# PH10EA2332-1.net
KiCad netlist of a schematic drawn in Altium Designer
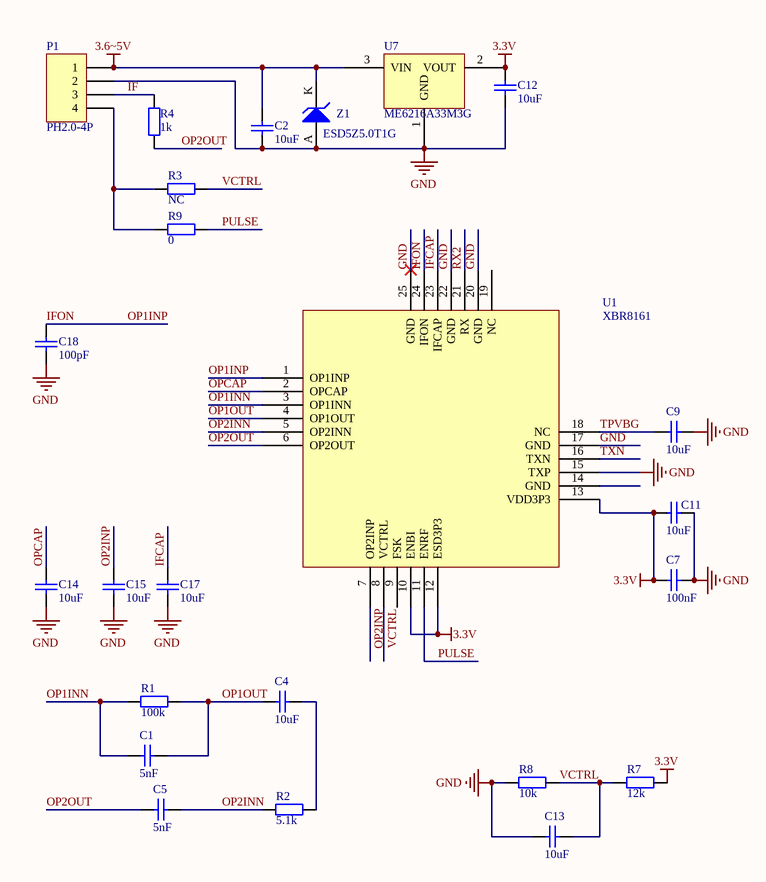
[diagram p0: PH10EA2332-1.SchDoc]

(export (version "E")
  (design (tool "Eeschema 10.0.6"))
  (components
    (comp (ref "C1")
      (value "5nF")
      (footprint "C0402")
      (description "Capacitor")
      (fields (field (name "PUBLISHER") "Altium Limited"))
      (libsource (lib "Miscellaneous Devices") (part "Cap"))
    )
    (comp (ref "C2")
      (value "10uF")
      (footprint "C0402")
      (description "Capacitor")
      (fields (field (name "PUBLISHER") "Altium Limited"))
      (libsource (lib "Miscellaneous Devices") (part "Cap"))
    )
    (comp (ref "C4")
      (value "10uF")
      (footprint "C0402")
      (description "Capacitor")
      (fields (field (name "PUBLISHER") "Altium Limited"))
      (libsource (lib "Miscellaneous Devices") (part "Cap"))
    )
    (comp (ref "C5")
      (value "5nF")
      (footprint "C0402")
      (description "Capacitor")
      (fields (field (name "PUBLISHER") "Altium Limited"))
      (libsource (lib "Miscellaneous Devices") (part "Cap"))
    )
    (comp (ref "C7")
      (value "100nF")
      (footprint "C0402")
      (description "Capacitor")
      (fields (field (name "PUBLISHER") "Altium Limited"))
      (libsource (lib "Miscellaneous Devices") (part "Cap"))
    )
    (comp (ref "C9")
      (value "10uF")
      (footprint "C0402")
      (description "Capacitor")
      (fields (field (name "PUBLISHER") "Altium Limited"))
      (libsource (lib "Miscellaneous Devices") (part "Cap"))
    )
    (comp (ref "C11")
      (value "10uF")
      (footprint "C0402")
      (description "Capacitor")
      (fields (field (name "PUBLISHER") "Altium Limited"))
      (libsource (lib "Miscellaneous Devices") (part "Cap"))
    )
    (comp (ref "C12")
      (value "10uF")
      (footprint "C0402")
      (description "Capacitor")
      (fields (field (name "PUBLISHER") "Altium Limited"))
      (libsource (lib "Miscellaneous Devices") (part "Cap"))
    )
    (comp (ref "C13")
      (value "10uF")
      (footprint "C0402")
      (description "Capacitor")
      (fields (field (name "PUBLISHER") "Altium Limited"))
      (libsource (lib "Miscellaneous Devices") (part "Cap"))
    )
    (comp (ref "C14")
      (value "10uF")
      (footprint "C0402")
      (description "Capacitor")
      (fields (field (name "PUBLISHER") "Altium Limited"))
      (libsource (lib "Miscellaneous Devices") (part "Cap"))
    )
    (comp (ref "C15")
      (value "10uF")
      (footprint "C0402")
      (description "Capacitor")
      (fields (field (name "PUBLISHER") "Altium Limited"))
      (libsource (lib "Miscellaneous Devices") (part "Cap"))
    )
    (comp (ref "C17")
      (value "10uF")
      (footprint "C0402")
      (description "Capacitor")
      (fields (field (name "PUBLISHER") "Altium Limited"))
      (libsource (lib "Miscellaneous Devices") (part "Cap"))
    )
    (comp (ref "C18")
      (value "100pF")
      (footprint "C0402")
      (description "Capacitor")
      (fields (field (name "PUBLISHER") "Altium Limited"))
      (libsource (lib "Miscellaneous Devices") (part "Cap"))
    )
    (comp (ref "P1")
      (value "PH2.0-4P")
      (footprint "PH2.0-4P")
      (description "Header, 4-Pin")
      (fields (field (name "PUBLISHER") "Altium Limited"))
      (libsource (lib "*") (part "Header 4"))
    )
    (comp (ref "R1")
      (value "100k")
      (footprint "R0402")
      (description "Resistor")
      (fields (field (name "PUBLISHER") "Altium Limited"))
      (libsource (lib "Miscellaneous Devices") (part "Res2"))
    )
    (comp (ref "R2")
      (value "5.1k")
      (footprint "R0402")
      (description "Resistor")
      (fields (field (name "PUBLISHER") "Altium Limited"))
      (libsource (lib "") (part "Res2_2"))
    )
    (comp (ref "R3")
      (value "NC")
      (footprint "R0402")
      (description "Resistor")
      (fields (field (name "PUBLISHER") "Altium Limited"))
      (libsource (lib "") (part "Res2_2"))
    )
    (comp (ref "R4")
      (value "1k")
      (footprint "R0402")
      (description "Resistor")
      (fields (field (name "PUBLISHER") "Altium Limited"))
      (libsource (lib "") (part "Res2_1"))
    )
    (comp (ref "R7")
      (value "12k")
      (footprint "R0402")
      (description "Resistor")
      (fields (field (name "PUBLISHER") "Altium Limited"))
      (libsource (lib "") (part "Res2_2"))
    )
    (comp (ref "R8")
      (value "10k")
      (footprint "R0402")
      (description "Resistor")
      (fields (field (name "PUBLISHER") "Altium Limited"))
      (libsource (lib "") (part "Res2_2"))
    )
    (comp (ref "R9")
      (value "0")
      (footprint "R0402")
      (description "Resistor")
      (fields (field (name "PUBLISHER") "Altium Limited"))
      (libsource (lib "Miscellaneous Devices") (part "Res2"))
    )
    (comp (ref "U1")
      (value "XBR8161")
      (footprint "QFN24")
      (libsource (lib "altium-import") (part "root_0_XBR8161_"))
    )
    (comp (ref "U7")
      (value "ME6216A33M3G")
      (footprint "SOT-23-L")
      (libsource (lib "Schlib1") (part "SSP6206"))
    )
    (comp (ref "Z1")
      (value "ESD5Z5.0T1G")
      (footprint "SOD-523")
      (description "Zener Diode")
      (fields (field (name "PUBLISHER") "Altium Limited"))
      (libsource (lib "Miscellaneous Devices") (part "D Zener"))
    )
  )
  (nets
    (net (code "1") (name "/IF") (class "Default")
      (node (ref "P1") (pin "3") (pinfunction "3_3") (pintype "passive"))
      (node (ref "R4") (pin "1") (pinfunction "1_1") (pintype "passive"))
    )
    (net (code "2") (name "/IFCAP") (class "Default")
      (node (ref "C17") (pin "2") (pinfunction "2_2") (pintype "passive"))
      (node (ref "U1") (pin "23") (pinfunction "IFCAP_23") (pintype "passive"))
    )
    (net (code "3") (name "/IFON") (class "Default")
      (node (ref "C18") (pin "2") (pinfunction "2_2") (pintype "passive"))
      (node (ref "U1") (pin "1") (pinfunction "OP1INP_1") (pintype "passive"))
      (node (ref "U1") (pin "24") (pinfunction "IFON_24") (pintype "passive"))
    )
    (net (code "4") (name "/OP1INN") (class "Default")
      (node (ref "C1") (pin "2") (pinfunction "2_2") (pintype "passive"))
      (node (ref "R1") (pin "1") (pinfunction "1_1") (pintype "passive"))
      (node (ref "U1") (pin "3") (pinfunction "OP1INN_3") (pintype "passive"))
    )
    (net (code "5") (name "/OP1OUT") (class "Default")
      (node (ref "C1") (pin "1") (pinfunction "1_1") (pintype "passive"))
      (node (ref "C4") (pin "2") (pinfunction "2_2") (pintype "passive"))
      (node (ref "R1") (pin "2") (pinfunction "2_2") (pintype "passive"))
      (node (ref "U1") (pin "4") (pinfunction "OP1OUT_4") (pintype "passive"))
    )
    (net (code "6") (name "/OP2INN") (class "Default")
      (node (ref "C5") (pin "2") (pinfunction "2_2") (pintype "passive"))
      (node (ref "R2") (pin "2") (pinfunction "2_2") (pintype "passive"))
      (node (ref "U1") (pin "5") (pinfunction "OP2INN_5") (pintype "passive"))
    )
    (net (code "7") (name "/OP2INP") (class "Default")
      (node (ref "C15") (pin "1") (pinfunction "1_1") (pintype "passive"))
      (node (ref "U1") (pin "7") (pinfunction "OP2INP_7") (pintype "passive"))
    )
    (net (code "8") (name "/OP2OUT") (class "Default")
      (node (ref "C5") (pin "1") (pinfunction "1_1") (pintype "passive"))
      (node (ref "R4") (pin "2") (pinfunction "2_2") (pintype "passive"))
      (node (ref "U1") (pin "6") (pinfunction "OP2OUT_6") (pintype "passive"))
    )
    (net (code "9") (name "/OPCAP") (class "Default")
      (node (ref "C14") (pin "2") (pinfunction "2_2") (pintype "passive"))
      (node (ref "U1") (pin "2") (pinfunction "OPCAP_2") (pintype "passive"))
    )
    (net (code "10") (name "/PULSE") (class "Default")
      (node (ref "R9") (pin "2") (pinfunction "2_2") (pintype "passive"))
      (node (ref "U1") (pin "11") (pinfunction "ENRF_11") (pintype "passive"))
    )
    (net (code "11") (name "/RX2") (class "Default")
      (node (ref "U1") (pin "21") (pinfunction "RX_21") (pintype "passive"))
    )
    (net (code "12") (name "/TPVBG") (class "Default")
      (node (ref "C9") (pin "2") (pinfunction "2_2") (pintype "passive"))
      (node (ref "U1") (pin "18") (pinfunction "NC_18") (pintype "passive"))
    )
    (net (code "13") (name "/TXN") (class "Default")
      (node (ref "U1") (pin "16") (pinfunction "TXN_16") (pintype "passive"))
    )
    (net (code "14") (name "/VCTRL") (class "Default")
      (node (ref "C13") (pin "1") (pinfunction "1_1") (pintype "passive"))
      (node (ref "R3") (pin "1") (pinfunction "1_1") (pintype "passive"))
      (node (ref "R7") (pin "2") (pinfunction "2_2") (pintype "passive"))
      (node (ref "R8") (pin "1") (pinfunction "1_1") (pintype "passive"))
      (node (ref "U1") (pin "8") (pinfunction "VCTRL_8") (pintype "passive"))
    )
    (net (code "15") (name "3.3V") (class "Default")
      (node (ref "C11") (pin "2") (pinfunction "2_2") (pintype "passive"))
      (node (ref "C12") (pin "1") (pinfunction "1_1") (pintype "passive"))
      (node (ref "C7") (pin "2") (pinfunction "2_2") (pintype "passive"))
      (node (ref "R7") (pin "1") (pinfunction "1_1") (pintype "passive"))
      (node (ref "U1") (pin "10") (pinfunction "ENBI_10") (pintype "passive"))
      (node (ref "U1") (pin "12") (pinfunction "ESD3P3_12") (pintype "passive"))
      (node (ref "U1") (pin "13") (pinfunction "VDD3P3_13") (pintype "passive"))
      (node (ref "U7") (pin "2") (pinfunction "VOUT_2") (pintype "passive"))
    )
    (net (code "16") (name "3.6~5V") (class "Default")
      (node (ref "C2") (pin "1") (pinfunction "1_1") (pintype "passive"))
      (node (ref "P1") (pin "1") (pinfunction "1_1") (pintype "passive"))
      (node (ref "U7") (pin "3") (pinfunction "VIN_3") (pintype "passive"))
      (node (ref "Z1") (pin "K") (pinfunction "K_K") (pintype "passive"))
    )
    (net (code "17") (name "GND") (class "Default")
      (node (ref "C11") (pin "1") (pinfunction "1_1") (pintype "passive"))
      (node (ref "C12") (pin "2") (pinfunction "2_2") (pintype "passive"))
      (node (ref "C13") (pin "2") (pinfunction "2_2") (pintype "passive"))
      (node (ref "C14") (pin "1") (pinfunction "1_1") (pintype "passive"))
      (node (ref "C15") (pin "2") (pinfunction "2_2") (pintype "passive"))
      (node (ref "C17") (pin "1") (pinfunction "1_1") (pintype "passive"))
      (node (ref "C18") (pin "1") (pinfunction "1_1") (pintype "passive"))
      (node (ref "C2") (pin "2") (pinfunction "2_2") (pintype "passive"))
      (node (ref "C7") (pin "1") (pinfunction "1_1") (pintype "passive"))
      (node (ref "C9") (pin "1") (pinfunction "1_1") (pintype "passive"))
      (node (ref "P1") (pin "2") (pinfunction "2_2") (pintype "passive"))
      (node (ref "R8") (pin "2") (pinfunction "2_2") (pintype "passive"))
      (node (ref "U1") (pin "15") (pinfunction "TXP_15") (pintype "passive"))
      (node (ref "U1") (pin "17") (pinfunction "GND_17") (pintype "passive"))
      (node (ref "U1") (pin "20") (pinfunction "GND_20") (pintype "passive"))
      (node (ref "U1") (pin "22") (pinfunction "GND_22") (pintype "passive"))
      (node (ref "U1") (pin "25") (pinfunction "GND_25") (pintype "passive"))
      (node (ref "U7") (pin "1") (pinfunction "GND_1") (pintype "passive"))
      (node (ref "Z1") (pin "A") (pinfunction "A_A") (pintype "passive"))
    )
    (net (code "18") (name "Net-(C4-Pad1)") (class "Default")
      (node (ref "C4") (pin "1") (pinfunction "1_1") (pintype "passive"))
      (node (ref "R2") (pin "1") (pinfunction "1_1") (pintype "passive"))
    )
    (net (code "19") (name "Net-(P1-Pad4)") (class "Default")
      (node (ref "P1") (pin "4") (pinfunction "4_4") (pintype "passive"))
      (node (ref "R3") (pin "2") (pinfunction "2_2") (pintype "passive"))
      (node (ref "R9") (pin "1") (pinfunction "1_1") (pintype "passive"))
    )
    (net (code "20") (name "unconnected-(U1-FSK-Pad9)") (class "Default")
      (node (ref "U1") (pin "9") (pinfunction "FSK_9") (pintype "passive"))
    )
    (net (code "21") (name "unconnected-(U1-GND-Pad14)") (class "Default")
      (node (ref "U1") (pin "14") (pinfunction "GND_14") (pintype "passive"))
    )
    (net (code "22") (name "unconnected-(U1-NC-Pad19)") (class "Default")
      (node (ref "U1") (pin "19") (pinfunction "NC_19") (pintype "passive"))
    )
  )
)
